# a2402-4069-overdrive.net
KiCad netlist of a schematic drawn in EAGLE
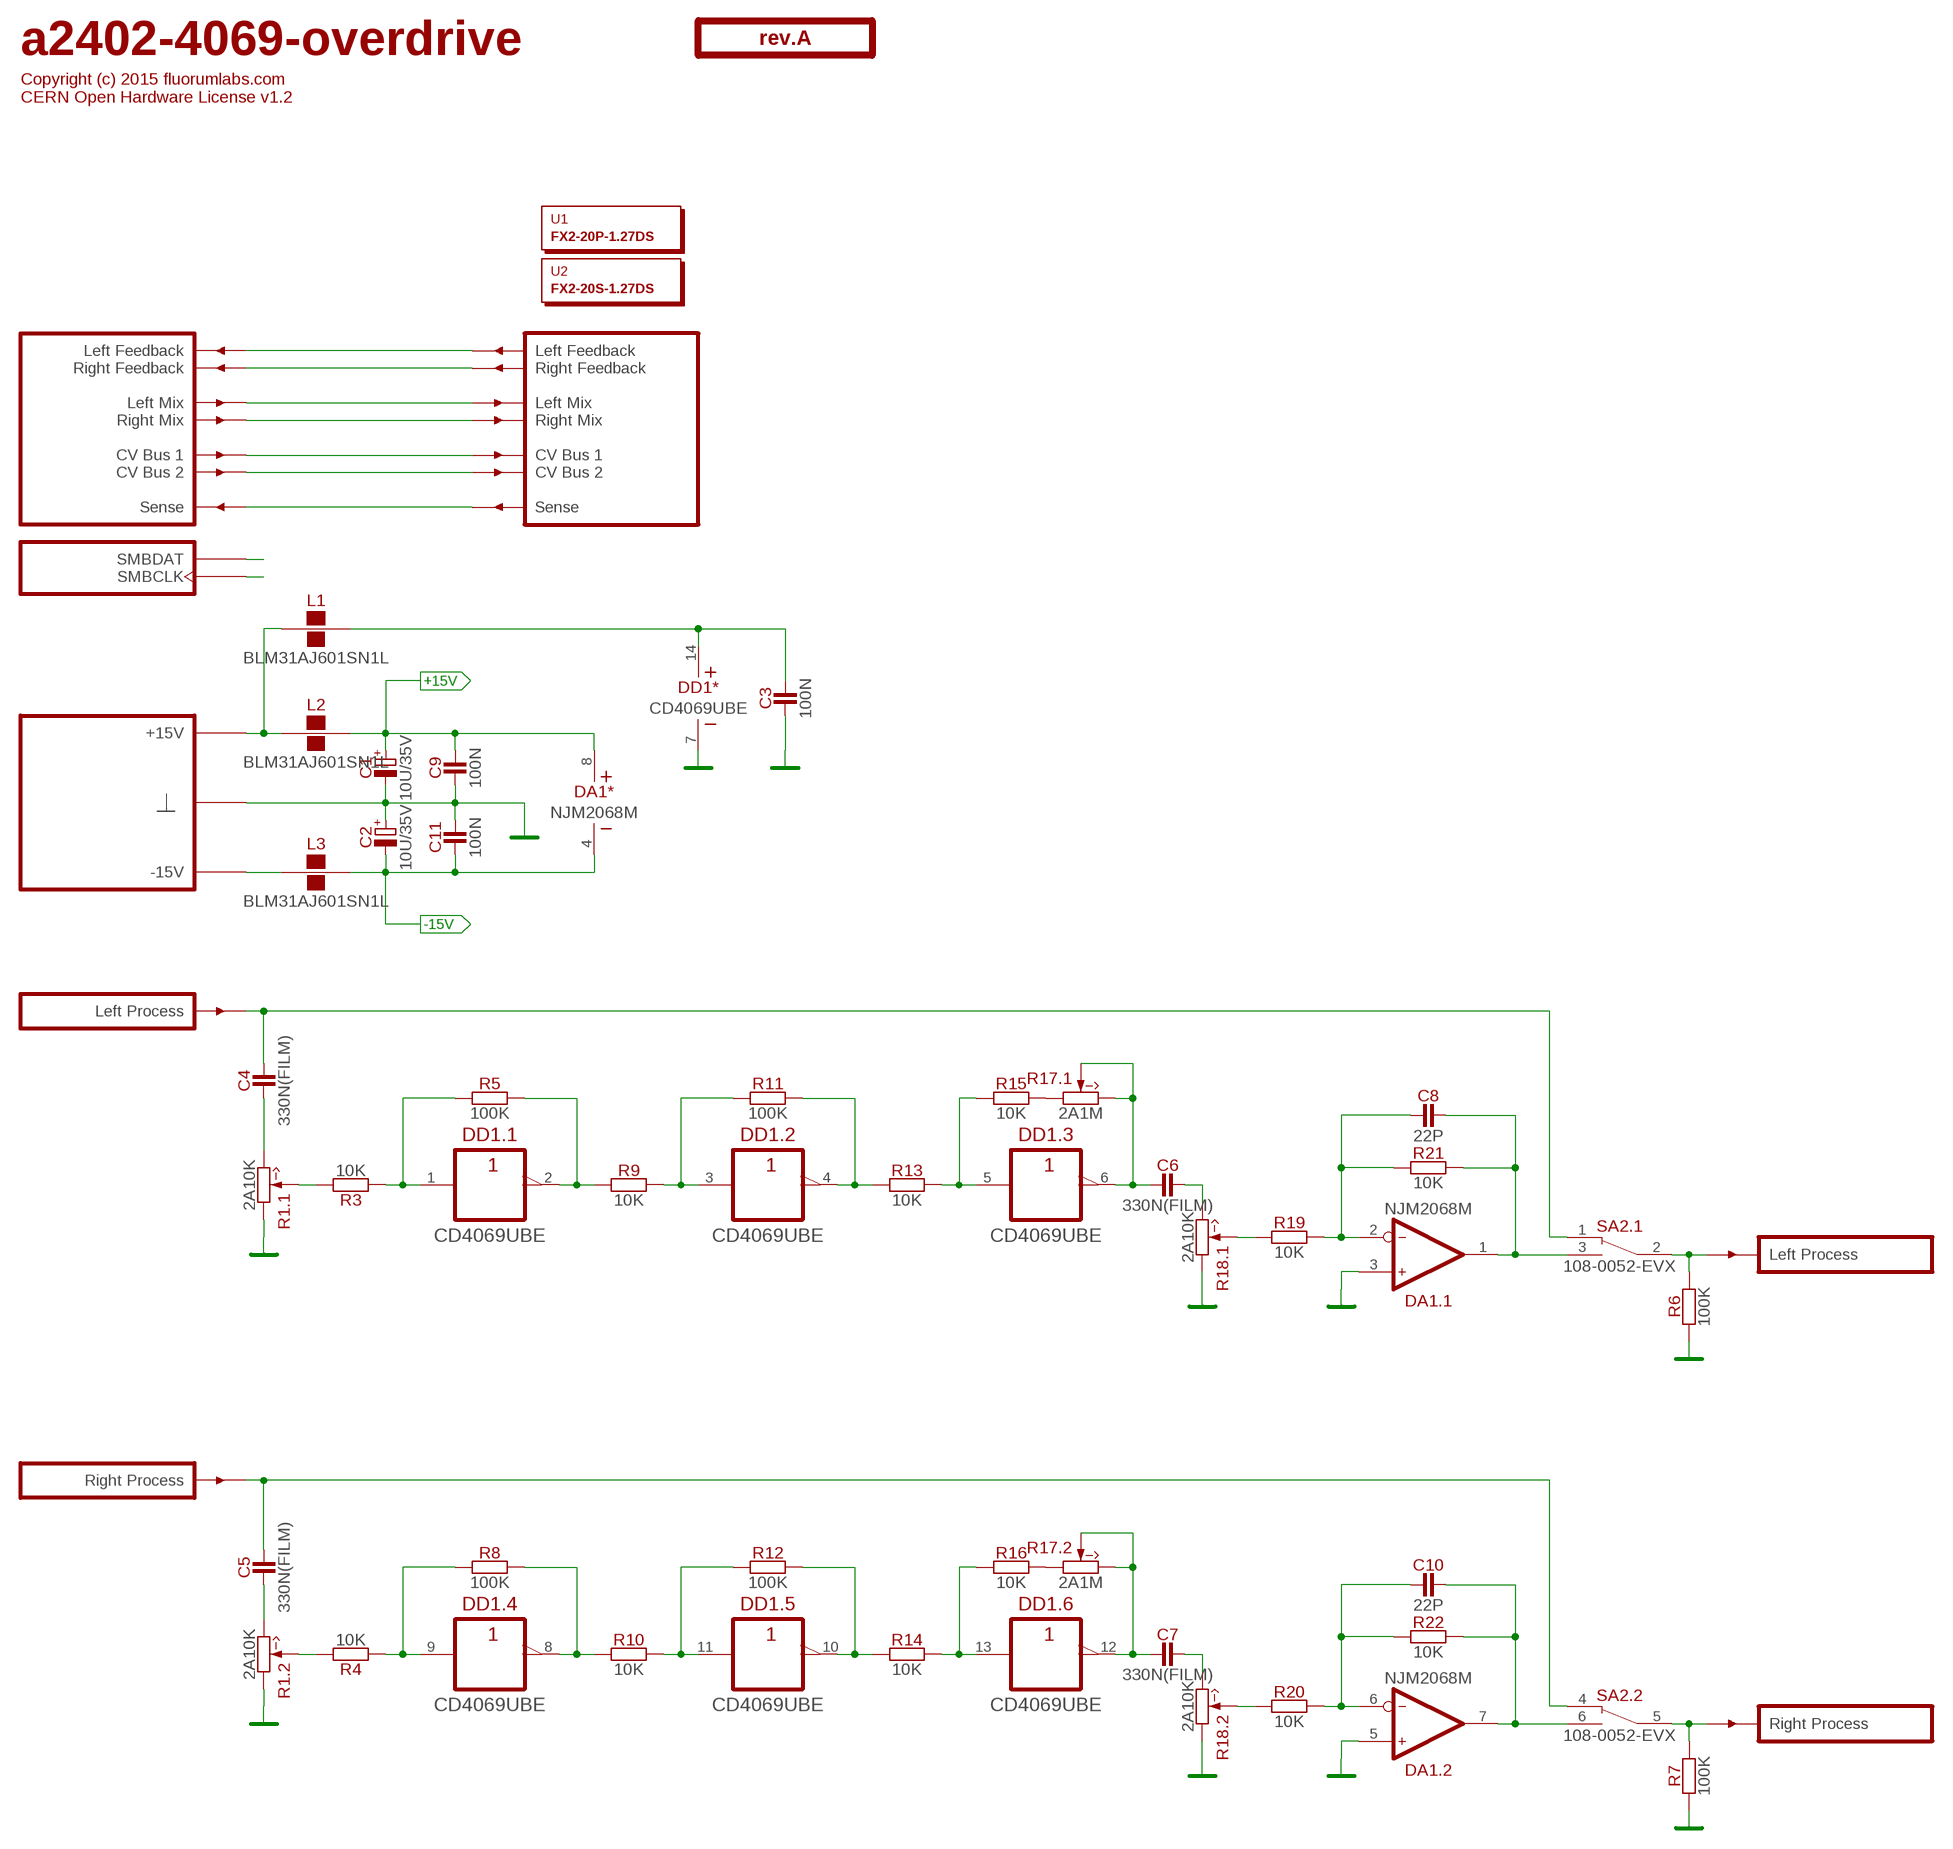
[diagram p0: schematic, sheet 1]

(export (version "E")
  (design (tool "Eeschema 10.0.6"))
  (components
    (comp (ref "C1")
      (value "10U/35V")
      (footprint "eagle-import:E2-5")
      (libsource (lib "eagle-import") (part "?10U/35V"))
    )
    (comp (ref "C2")
      (value "10U/35V")
      (footprint "eagle-import:E2-5")
      (libsource (lib "eagle-import") (part "?10U/35V"))
    )
    (comp (ref "C3")
      (value "100N")
      (footprint "eagle-import:C-0805")
      (libsource (lib "eagle-import") (part "?100N"))
    )
    (comp (ref "C4")
      (value "330N(FILM)")
      (footprint "eagle-import:C050-035X075")
      (libsource (lib "eagle-import") (part "?330N(FILM)"))
    )
    (comp (ref "C5")
      (value "330N(FILM)")
      (footprint "eagle-import:C050-035X075")
      (libsource (lib "eagle-import") (part "?330N(FILM)"))
    )
    (comp (ref "C6")
      (value "330N(FILM)")
      (footprint "eagle-import:C050-035X075")
      (libsource (lib "eagle-import") (part "?330N(FILM)"))
    )
    (comp (ref "C7")
      (value "330N(FILM)")
      (footprint "eagle-import:C050-035X075")
      (libsource (lib "eagle-import") (part "?330N(FILM)"))
    )
    (comp (ref "C8")
      (value "22P")
      (footprint "eagle-import:C-0805")
      (libsource (lib "eagle-import") (part "?22P"))
    )
    (comp (ref "C9")
      (value "100N")
      (footprint "eagle-import:C-0805")
      (libsource (lib "eagle-import") (part "?100N"))
    )
    (comp (ref "C10")
      (value "22P")
      (footprint "eagle-import:C-0805")
      (libsource (lib "eagle-import") (part "?22P"))
    )
    (comp (ref "C11")
      (value "100N")
      (footprint "eagle-import:C-0805")
      (libsource (lib "eagle-import") (part "?100N"))
    )
    (comp (ref "DA1")
      (value "NJM2068M")
      (footprint "eagle-import:SO-8")
      (libsource (lib "eagle-import") (part "NJM2068M"))
    )
    (comp (ref "DD1")
      (value "CD4069UBE")
      (footprint "eagle-import:DIP-14")
      (libsource (lib "eagle-import") (part "CD4069UBE"))
    )
    (comp (ref "L1")
      (value "BLM31AJ601SN1L")
      (footprint "eagle-import:1206")
      (libsource (lib "eagle-import") (part "BLM31AJ601SN1L"))
    )
    (comp (ref "L2")
      (value "BLM31AJ601SN1L")
      (footprint "eagle-import:1206")
      (libsource (lib "eagle-import") (part "BLM31AJ601SN1L"))
    )
    (comp (ref "L3")
      (value "BLM31AJ601SN1L")
      (footprint "eagle-import:1206")
      (libsource (lib "eagle-import") (part "BLM31AJ601SN1L"))
    )
    (comp (ref "O1")
      (value "TITLE")
      (footprint "eagle-import:EMPTY")
      (libsource (lib "eagle-import") (part "TITLE"))
    )
    (comp (ref "PCB1")
      (value "rev.A")
      (footprint "eagle-import:ST2-BOARD-50")
      (libsource (lib "eagle-import") (part "ST2-BOARD-50"))
    )
    (comp (ref "R1")
      (value "2A10K")
      (footprint "eagle-import:RV11-DUAL")
      (libsource (lib "eagle-import") (part "2?A10K"))
    )
    (comp (ref "R3")
      (value "10K")
      (footprint "eagle-import:R-0805")
      (libsource (lib "eagle-import") (part "?10K"))
    )
    (comp (ref "R4")
      (value "10K")
      (footprint "eagle-import:R-0805")
      (libsource (lib "eagle-import") (part "?10K"))
    )
    (comp (ref "R5")
      (value "100K")
      (footprint "eagle-import:R-0805")
      (libsource (lib "eagle-import") (part "?100K"))
    )
    (comp (ref "R6")
      (value "100K")
      (footprint "eagle-import:R-0805")
      (libsource (lib "eagle-import") (part "?100K"))
    )
    (comp (ref "R7")
      (value "100K")
      (footprint "eagle-import:R-0805")
      (libsource (lib "eagle-import") (part "?100K"))
    )
    (comp (ref "R8")
      (value "100K")
      (footprint "eagle-import:R-0805")
      (libsource (lib "eagle-import") (part "?100K"))
    )
    (comp (ref "R9")
      (value "10K")
      (footprint "eagle-import:R-0805")
      (libsource (lib "eagle-import") (part "?10K"))
    )
    (comp (ref "R10")
      (value "10K")
      (footprint "eagle-import:R-0805")
      (libsource (lib "eagle-import") (part "?10K"))
    )
    (comp (ref "R11")
      (value "100K")
      (footprint "eagle-import:R-0805")
      (libsource (lib "eagle-import") (part "?100K"))
    )
    (comp (ref "R12")
      (value "100K")
      (footprint "eagle-import:R-0805")
      (libsource (lib "eagle-import") (part "?100K"))
    )
    (comp (ref "R13")
      (value "10K")
      (footprint "eagle-import:R-0805")
      (libsource (lib "eagle-import") (part "?10K"))
    )
    (comp (ref "R14")
      (value "10K")
      (footprint "eagle-import:R-0805")
      (libsource (lib "eagle-import") (part "?10K"))
    )
    (comp (ref "R15")
      (value "10K")
      (footprint "eagle-import:R-0805")
      (libsource (lib "eagle-import") (part "?10K"))
    )
    (comp (ref "R16")
      (value "10K")
      (footprint "eagle-import:R-0805")
      (libsource (lib "eagle-import") (part "?10K"))
    )
    (comp (ref "R17")
      (value "2A1M")
      (footprint "eagle-import:RV11-DUAL")
      (libsource (lib "eagle-import") (part "2?A1M"))
    )
    (comp (ref "R18")
      (value "2A10K")
      (footprint "eagle-import:RV11-DUAL")
      (libsource (lib "eagle-import") (part "2?A10K"))
    )
    (comp (ref "R19")
      (value "10K")
      (footprint "eagle-import:R-0805")
      (libsource (lib "eagle-import") (part "?10K"))
    )
    (comp (ref "R20")
      (value "10K")
      (footprint "eagle-import:R-0805")
      (libsource (lib "eagle-import") (part "?10K"))
    )
    (comp (ref "R21")
      (value "10K")
      (footprint "eagle-import:R-0805")
      (libsource (lib "eagle-import") (part "?10K"))
    )
    (comp (ref "R22")
      (value "10K")
      (footprint "eagle-import:R-0805")
      (libsource (lib "eagle-import") (part "?10K"))
    )
    (comp (ref "SA2")
      (value "108-0052-EVX")
      (footprint "eagle-import:108-0052-EVX")
      (libsource (lib "eagle-import") (part "108-0052-EVX"))
    )
    (comp (ref "U1")
      (value "FX2-20P-1.27DS")
      (footprint "eagle-import:EMPTY")
      (libsource (lib "eagle-import") (part "?FX2-20P-1.27DS"))
    )
    (comp (ref "U2")
      (value "FX2-20S-1.27DS")
      (footprint "eagle-import:EMPTY")
      (libsource (lib "eagle-import") (part "?FX2-20S-1.27DS"))
    )
  )
  (nets
    (net (code "1") (name "+15V") (class "Default")
      (node (ref "C1") (pin "+") (pinfunction "+_+") (pintype "passive"))
      (node (ref "C9") (pin "2") (pinfunction "2_2") (pintype "passive"))
      (node (ref "DA1") (pin "8") (pinfunction "V+_8") (pintype "power_in"))
      (node (ref "L2") (pin "2") (pinfunction "2_2") (pintype "passive"))
    )
    (net (code "2") (name "-15V") (class "Default")
      (node (ref "C11") (pin "1") (pinfunction "1_1") (pintype "passive"))
      (node (ref "C2") (pin "-") (pinfunction "-_-") (pintype "passive"))
      (node (ref "DA1") (pin "4") (pinfunction "V-_4") (pintype "power_in"))
      (node (ref "L3") (pin "2") (pinfunction "2_2") (pintype "passive"))
    )
    (net (code "3") (name "GND") (class "Default")
      (node (ref "C1") (pin "-") (pinfunction "-_-") (pintype "passive"))
      (node (ref "C11") (pin "2") (pinfunction "2_2") (pintype "passive"))
      (node (ref "C2") (pin "+") (pinfunction "+_+") (pintype "passive"))
      (node (ref "C3") (pin "1") (pinfunction "1_1") (pintype "passive"))
      (node (ref "C9") (pin "1") (pinfunction "1_1") (pintype "passive"))
      (node (ref "DA1") (pin "3") (pinfunction "IN+_3") (pintype "input"))
      (node (ref "DA1") (pin "5") (pinfunction "IN+_5") (pintype "input"))
      (node (ref "DD1") (pin "7") (pinfunction "V-_7") (pintype "power_in"))
      (node (ref "PCB1") (pin "B4") (pinfunction "GND_B4") (pintype "bidirectional"))
      (node (ref "PCB1") (pin "B4'") (pinfunction "GND_B4'") (pintype "bidirectional"))
      (node (ref "PCB1") (pin "B5") (pinfunction "GND_B5") (pintype "bidirectional"))
      (node (ref "PCB1") (pin "B5'") (pinfunction "GND_B5'") (pintype "bidirectional"))
      (node (ref "PCB1") (pin "B6") (pinfunction "GND_B6") (pintype "bidirectional"))
      (node (ref "PCB1") (pin "B6'") (pinfunction "GND_B6'") (pintype "bidirectional"))
      (node (ref "PCB1") (pin "B7") (pinfunction "GND_B7") (pintype "bidirectional"))
      (node (ref "PCB1") (pin "B7'") (pinfunction "GND_B7'") (pintype "bidirectional"))
      (node (ref "PCB1") (pin "B8") (pinfunction "GND_B8") (pintype "bidirectional"))
      (node (ref "PCB1") (pin "B8'") (pinfunction "GND_B8'") (pintype "bidirectional"))
      (node (ref "R1") (pin "1") (pinfunction "CCW_1") (pintype "passive"))
      (node (ref "R1") (pin "1'") (pinfunction "CCW_1'") (pintype "passive"))
      (node (ref "R18") (pin "1") (pinfunction "CCW_1") (pintype "passive"))
      (node (ref "R18") (pin "1'") (pinfunction "CCW_1'") (pintype "passive"))
      (node (ref "R6") (pin "2") (pinfunction "2_2") (pintype "passive"))
      (node (ref "R7") (pin "2") (pinfunction "2_2") (pintype "passive"))
    )
    (net (code "4") (name "Net-(DA1B-IN-)") (class "Default")
      (node (ref "C8") (pin "1") (pinfunction "1_1") (pintype "passive"))
      (node (ref "DA1") (pin "2") (pinfunction "IN-_2") (pintype "input"))
      (node (ref "R19") (pin "2") (pinfunction "2_2") (pintype "passive"))
      (node (ref "R21") (pin "1") (pinfunction "1_1") (pintype "passive"))
    )
    (net (code "5") (name "Net-(DA1B-OUT)") (class "Default")
      (node (ref "C8") (pin "2") (pinfunction "2_2") (pintype "passive"))
      (node (ref "DA1") (pin "1") (pinfunction "OUT_1") (pintype "output"))
      (node (ref "R21") (pin "2") (pinfunction "2_2") (pintype "passive"))
      (node (ref "SA2") (pin "3") (pinfunction "NO_3") (pintype "passive"))
    )
    (net (code "6") (name "Net-(DA1C-IN-)") (class "Default")
      (node (ref "C10") (pin "1") (pinfunction "1_1") (pintype "passive"))
      (node (ref "DA1") (pin "6") (pinfunction "IN-_6") (pintype "input"))
      (node (ref "R20") (pin "2") (pinfunction "2_2") (pintype "passive"))
      (node (ref "R22") (pin "1") (pinfunction "1_1") (pintype "passive"))
    )
    (net (code "7") (name "Net-(DA1C-OUT)") (class "Default")
      (node (ref "C10") (pin "2") (pinfunction "2_2") (pintype "passive"))
      (node (ref "DA1") (pin "7") (pinfunction "OUT_7") (pintype "output"))
      (node (ref "R22") (pin "2") (pinfunction "2_2") (pintype "passive"))
      (node (ref "SA2") (pin "6") (pinfunction "NO_6") (pintype "passive"))
    )
    (net (code "8") (name "Net-(DD1A-V+)") (class "Default")
      (node (ref "C3") (pin "2") (pinfunction "2_2") (pintype "passive"))
      (node (ref "DD1") (pin "14") (pinfunction "V+_14") (pintype "power_in"))
      (node (ref "L1") (pin "2") (pinfunction "2_2") (pintype "passive"))
    )
    (net (code "9") (name "Net-(DD1B-A)") (class "Default")
      (node (ref "DD1") (pin "1") (pinfunction "A_1") (pintype "input"))
      (node (ref "R3") (pin "1") (pinfunction "1_1") (pintype "passive"))
      (node (ref "R5") (pin "1") (pinfunction "1_1") (pintype "passive"))
    )
    (net (code "10") (name "Net-(DD1B-Y)") (class "Default")
      (node (ref "DD1") (pin "2") (pinfunction "Y_2") (pintype "output"))
      (node (ref "R5") (pin "2") (pinfunction "2_2") (pintype "passive"))
      (node (ref "R9") (pin "1") (pinfunction "1_1") (pintype "passive"))
    )
    (net (code "11") (name "Net-(DD1C-A)") (class "Default")
      (node (ref "DD1") (pin "3") (pinfunction "A_3") (pintype "input"))
      (node (ref "R11") (pin "1") (pinfunction "1_1") (pintype "passive"))
      (node (ref "R9") (pin "2") (pinfunction "2_2") (pintype "passive"))
    )
    (net (code "12") (name "Net-(DD1C-Y)") (class "Default")
      (node (ref "DD1") (pin "4") (pinfunction "Y_4") (pintype "output"))
      (node (ref "R11") (pin "2") (pinfunction "2_2") (pintype "passive"))
      (node (ref "R13") (pin "1") (pinfunction "1_1") (pintype "passive"))
    )
    (net (code "13") (name "Net-(DD1D-A)") (class "Default")
      (node (ref "DD1") (pin "5") (pinfunction "A_5") (pintype "input"))
      (node (ref "R13") (pin "2") (pinfunction "2_2") (pintype "passive"))
      (node (ref "R15") (pin "1") (pinfunction "1_1") (pintype "passive"))
    )
    (net (code "14") (name "Net-(DD1D-Y)") (class "Default")
      (node (ref "C6") (pin "1") (pinfunction "1_1") (pintype "passive"))
      (node (ref "DD1") (pin "6") (pinfunction "Y_6") (pintype "output"))
      (node (ref "R17") (pin "2") (pinfunction "W_2") (pintype "passive"))
      (node (ref "R17") (pin "3") (pinfunction "CW_3") (pintype "passive"))
    )
    (net (code "15") (name "Net-(DD1E-A)") (class "Default")
      (node (ref "DD1") (pin "9") (pinfunction "A_9") (pintype "input"))
      (node (ref "R4") (pin "1") (pinfunction "1_1") (pintype "passive"))
      (node (ref "R8") (pin "1") (pinfunction "1_1") (pintype "passive"))
    )
    (net (code "16") (name "Net-(DD1E-Y)") (class "Default")
      (node (ref "DD1") (pin "8") (pinfunction "Y_8") (pintype "output"))
      (node (ref "R10") (pin "1") (pinfunction "1_1") (pintype "passive"))
      (node (ref "R8") (pin "2") (pinfunction "2_2") (pintype "passive"))
    )
    (net (code "17") (name "Net-(DD1F-A)") (class "Default")
      (node (ref "DD1") (pin "11") (pinfunction "A_11") (pintype "input"))
      (node (ref "R10") (pin "2") (pinfunction "2_2") (pintype "passive"))
      (node (ref "R12") (pin "1") (pinfunction "1_1") (pintype "passive"))
    )
    (net (code "18") (name "Net-(DD1F-Y)") (class "Default")
      (node (ref "DD1") (pin "10") (pinfunction "Y_10") (pintype "output"))
      (node (ref "R12") (pin "2") (pinfunction "2_2") (pintype "passive"))
      (node (ref "R14") (pin "1") (pinfunction "1_1") (pintype "passive"))
    )
    (net (code "19") (name "Net-(DD1G-A)") (class "Default")
      (node (ref "DD1") (pin "13") (pinfunction "A_13") (pintype "input"))
      (node (ref "R14") (pin "2") (pinfunction "2_2") (pintype "passive"))
      (node (ref "R16") (pin "1") (pinfunction "1_1") (pintype "passive"))
    )
    (net (code "20") (name "Net-(DD1G-Y)") (class "Default")
      (node (ref "C7") (pin "1") (pinfunction "1_1") (pintype "passive"))
      (node (ref "DD1") (pin "12") (pinfunction "Y_12") (pintype "output"))
      (node (ref "R17") (pin "2'") (pinfunction "W_2'") (pintype "passive"))
      (node (ref "R17") (pin "3'") (pinfunction "CW_3'") (pintype "passive"))
    )
    (net (code "21") (name "Net-(L1-Pad1)") (class "Default")
      (node (ref "L1") (pin "1") (pinfunction "1_1") (pintype "passive"))
      (node (ref "L2") (pin "1") (pinfunction "1_1") (pintype "passive"))
      (node (ref "PCB1") (pin "A+15") (pinfunction "P+15V_A+15") (pintype "bidirectional"))
      (node (ref "PCB1") (pin "A+15'") (pinfunction "P+15V_A+15'") (pintype "bidirectional"))
      (node (ref "PCB1") (pin "B+15") (pinfunction "P+15V_B+15") (pintype "bidirectional"))
      (node (ref "PCB1") (pin "B+15'") (pinfunction "P+15V_B+15'") (pintype "bidirectional"))
    )
    (net (code "22") (name "Net-(L3-Pad1)") (class "Default")
      (node (ref "L3") (pin "1") (pinfunction "1_1") (pintype "passive"))
      (node (ref "PCB1") (pin "A-15") (pinfunction "P-15V_A-15") (pintype "bidirectional"))
      (node (ref "PCB1") (pin "A-15'") (pinfunction "P-15V_A-15'") (pintype "bidirectional"))
      (node (ref "PCB1") (pin "B-15") (pinfunction "P-15V_B-15") (pintype "bidirectional"))
      (node (ref "PCB1") (pin "B-15'") (pinfunction "P-15V_B-15'") (pintype "bidirectional"))
    )
    (net (code "23") (name "Net-(PCB1B-INL)") (class "Default")
      (node (ref "C4") (pin "2") (pinfunction "2_2") (pintype "passive"))
      (node (ref "PCB1") (pin "BINL") (pinfunction "INL_BINL") (pintype "bidirectional"))
      (node (ref "SA2") (pin "1") (pinfunction "NC_1") (pintype "passive"))
    )
    (net (code "24") (name "Net-(PCB1C-INR)") (class "Default")
      (node (ref "C5") (pin "2") (pinfunction "2_2") (pintype "passive"))
      (node (ref "PCB1") (pin "BINR") (pinfunction "INR_BINR") (pintype "bidirectional"))
      (node (ref "SA2") (pin "4") (pinfunction "NC_4") (pintype "passive"))
    )
    (net (code "25") (name "Net-(PCB1D-OUTL)") (class "Default")
      (node (ref "PCB1") (pin "BOUTL'") (pinfunction "OUTL_BOUTL'") (pintype "bidirectional"))
      (node (ref "R6") (pin "1") (pinfunction "1_1") (pintype "passive"))
      (node (ref "SA2") (pin "2") (pinfunction "CM_2") (pintype "passive"))
    )
    (net (code "26") (name "Net-(PCB1E-OUTR)") (class "Default")
      (node (ref "PCB1") (pin "BOUTR'") (pinfunction "OUTR_BOUTR'") (pintype "bidirectional"))
      (node (ref "R7") (pin "1") (pinfunction "1_1") (pintype "passive"))
      (node (ref "SA2") (pin "5") (pinfunction "CM_5") (pintype "passive"))
    )
    (net (code "27") (name "Net-(PCB1F-CV1)") (class "Default")
      (node (ref "PCB1") (pin "ACV1") (pinfunction "CV1_ACV1") (pintype "bidirectional"))
      (node (ref "PCB1") (pin "ACV1'") (pinfunction "CV1'_ACV1'") (pintype "bidirectional"))
    )
    (net (code "28") (name "Net-(PCB1F-CV2)") (class "Default")
      (node (ref "PCB1") (pin "ACV2") (pinfunction "CV2_ACV2") (pintype "bidirectional"))
      (node (ref "PCB1") (pin "ACV2'") (pinfunction "CV2'_ACV2'") (pintype "bidirectional"))
    )
    (net (code "29") (name "Net-(PCB1F-LFBK)") (class "Default")
      (node (ref "PCB1") (pin "ALFBK") (pinfunction "LFBK_ALFBK") (pintype "bidirectional"))
      (node (ref "PCB1") (pin "ALFBK'") (pinfunction "LFBK'_ALFBK'") (pintype "bidirectional"))
    )
    (net (code "30") (name "Net-(PCB1F-LMIX)") (class "Default")
      (node (ref "PCB1") (pin "ALMIX") (pinfunction "LMIX_ALMIX") (pintype "bidirectional"))
      (node (ref "PCB1") (pin "ALMIX'") (pinfunction "LMIX'_ALMIX'") (pintype "bidirectional"))
    )
    (net (code "31") (name "Net-(PCB1F-RFBK)") (class "Default")
      (node (ref "PCB1") (pin "ARFBK") (pinfunction "RFBK_ARFBK") (pintype "bidirectional"))
      (node (ref "PCB1") (pin "ARFBK'") (pinfunction "RFBK'_ARFBK'") (pintype "bidirectional"))
    )
    (net (code "32") (name "Net-(PCB1F-RMIX)") (class "Default")
      (node (ref "PCB1") (pin "ARMIX") (pinfunction "RMIX_ARMIX") (pintype "bidirectional"))
      (node (ref "PCB1") (pin "ARMIX'") (pinfunction "RMIX'_ARMIX'") (pintype "bidirectional"))
    )
    (net (code "33") (name "Net-(PCB1F-SENSE)") (class "Default")
      (node (ref "PCB1") (pin "BSENSE") (pinfunction "SENSE_BSENSE") (pintype "bidirectional"))
      (node (ref "PCB1") (pin "BSENSE'") (pinfunction "SENSE'_BSENSE'") (pintype "bidirectional"))
    )
    (net (code "34") (name "Net-(PCB1H-SMBCLK-PadASMBCLK')") (class "Default")
      (node (ref "PCB1") (pin "ASMBCLK") (pinfunction "SMBCLK_ASMBCLK") (pintype "bidirectional"))
      (node (ref "PCB1") (pin "ASMBCLK'") (pinfunction "SMBCLK_ASMBCLK'") (pintype "bidirectional"))
    )
    (net (code "35") (name "Net-(PCB1H-SMBDAT-PadASMBDAT')") (class "Default")
      (node (ref "PCB1") (pin "ASMBDAT") (pinfunction "SMBDAT_ASMBDAT") (pintype "bidirectional"))
      (node (ref "PCB1") (pin "ASMBDAT'") (pinfunction "SMBDAT_ASMBDAT'") (pintype "bidirectional"))
    )
    (net (code "36") (name "Net-(R1A-CW)") (class "Default")
      (node (ref "C4") (pin "1") (pinfunction "1_1") (pintype "passive"))
      (node (ref "R1") (pin "3") (pinfunction "CW_3") (pintype "passive"))
    )
    (net (code "37") (name "Net-(R1A-W)") (class "Default")
      (node (ref "R1") (pin "2") (pinfunction "W_2") (pintype "passive"))
      (node (ref "R3") (pin "2") (pinfunction "2_2") (pintype "passive"))
    )
    (net (code "38") (name "Net-(R1B-CW)") (class "Default")
      (node (ref "C5") (pin "1") (pinfunction "1_1") (pintype "passive"))
      (node (ref "R1") (pin "3'") (pinfunction "CW_3'") (pintype "passive"))
    )
    (net (code "39") (name "Net-(R1B-W)") (class "Default")
      (node (ref "R1") (pin "2'") (pinfunction "W_2'") (pintype "passive"))
      (node (ref "R4") (pin "2") (pinfunction "2_2") (pintype "passive"))
    )
    (net (code "40") (name "Net-(R17A-CCW)") (class "Default")
      (node (ref "R15") (pin "2") (pinfunction "2_2") (pintype "passive"))
      (node (ref "R17") (pin "1") (pinfunction "CCW_1") (pintype "passive"))
    )
    (net (code "41") (name "Net-(R17B-CCW)") (class "Default")
      (node (ref "R16") (pin "2") (pinfunction "2_2") (pintype "passive"))
      (node (ref "R17") (pin "1'") (pinfunction "CCW_1'") (pintype "passive"))
    )
    (net (code "42") (name "Net-(R18A-CW)") (class "Default")
      (node (ref "C6") (pin "2") (pinfunction "2_2") (pintype "passive"))
      (node (ref "R18") (pin "3") (pinfunction "CW_3") (pintype "passive"))
    )
    (net (code "43") (name "Net-(R18A-W)") (class "Default")
      (node (ref "R18") (pin "2") (pinfunction "W_2") (pintype "passive"))
      (node (ref "R19") (pin "1") (pinfunction "1_1") (pintype "passive"))
    )
    (net (code "44") (name "Net-(R18B-CW)") (class "Default")
      (node (ref "C7") (pin "2") (pinfunction "2_2") (pintype "passive"))
      (node (ref "R18") (pin "3'") (pinfunction "CW_3'") (pintype "passive"))
    )
    (net (code "45") (name "Net-(R18B-W)") (class "Default")
      (node (ref "R18") (pin "2'") (pinfunction "W_2'") (pintype "passive"))
      (node (ref "R20") (pin "1") (pinfunction "1_1") (pintype "passive"))
    )
  )
)
